# DAC.net
KiCad netlist of a schematic drawn in Altium Designer
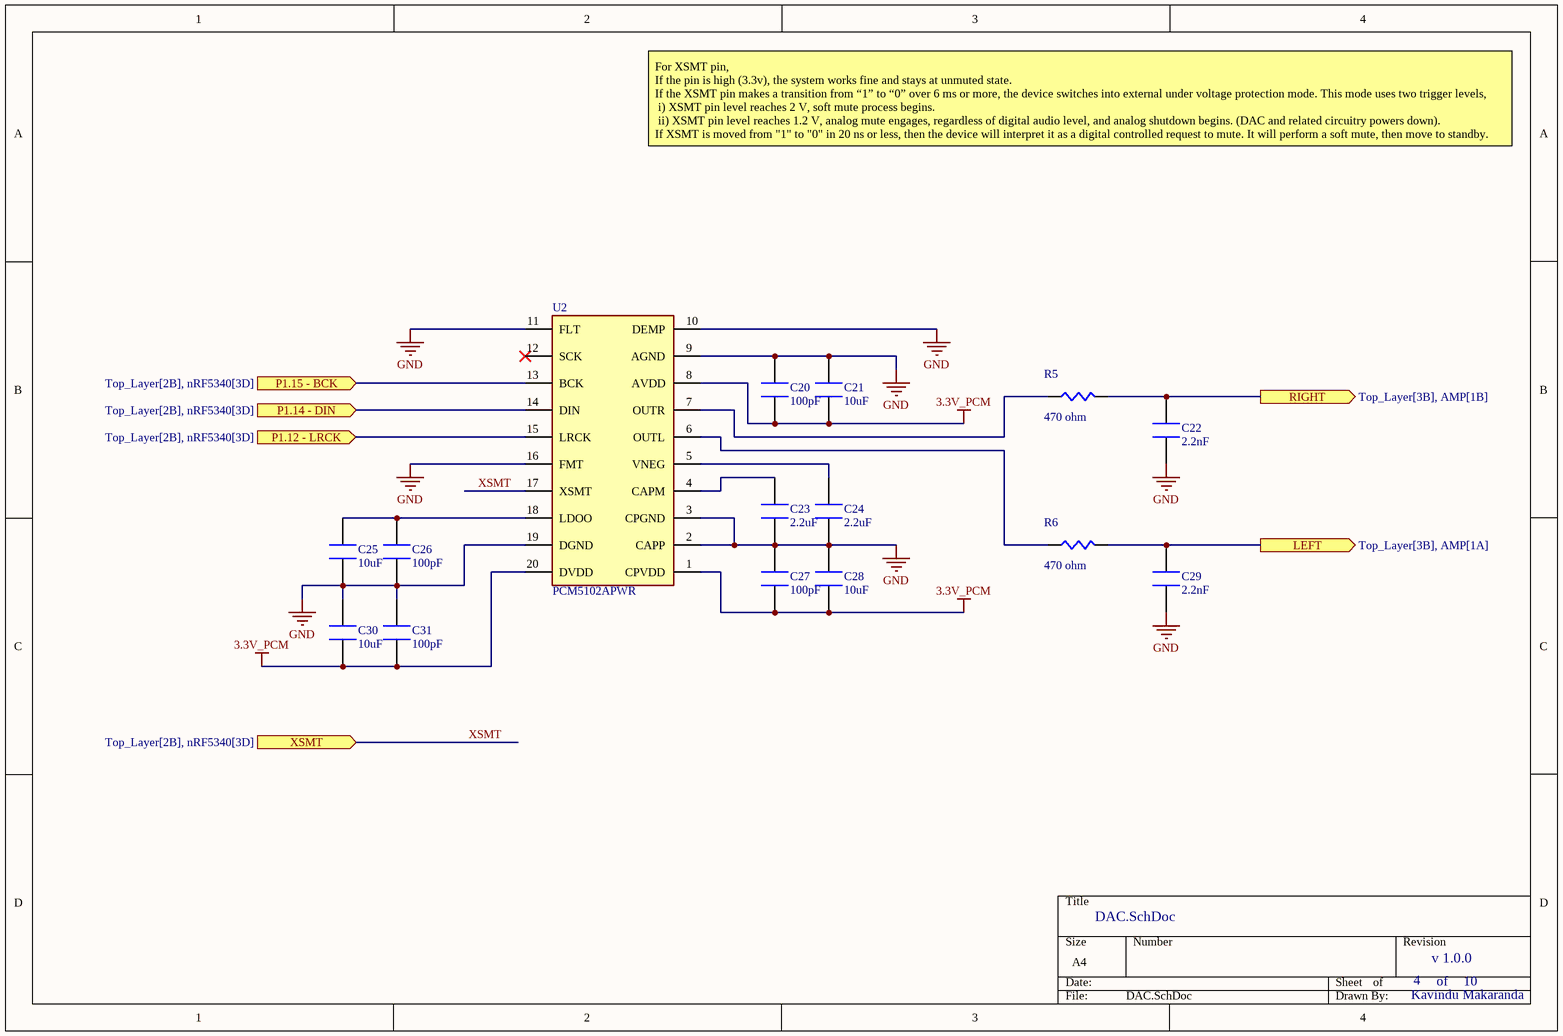
[diagram p0: DAC.SchDoc]

(export (version "E")
  (design (tool "Eeschema 10.0.6"))
  (components
    (comp (ref "C20")
      (value "100pF")
      (footprint "CAPC0603X8N")
      (libsource (lib "Schlib1") (part "CC0603_100pF_X7R"))
    )
    (comp (ref "C21")
      (value "10uF")
      (footprint "CAPC0805X14N")
      (description "C95841, CL21B106KOQNNNE, 10uF 16V X7R ±10% 0805 Multilayer Ceramic Capacitors MLCC - SMD/SMT ROHS")
      (libsource (lib "Schlib1") (part "CC0805_10uF_X7R"))
    )
    (comp (ref "C22")
      (value "2.2nF")
      (footprint "CAPC0603X8N")
      (libsource (lib "Schlib1") (part "CC0603_2.2nF_NPO"))
    )
    (comp (ref "C23")
      (value "2.2uF")
      (footprint "CAP0805X13N")
      (description "C19110 ,CL21B225KAFNNNE, 2.2uF 25V X7R ±10% 0805 Multilayer Ceramic Capacitors MLCC - SMD/SMT ROHS")
      (libsource (lib "Schlib1") (part "CC0805_2.2uF_X7R"))
    )
    (comp (ref "C24")
      (value "2.2uF")
      (footprint "CAP0805X13N")
      (description "C19110 ,CL21B225KAFNNNE, 2.2uF 25V X7R ±10% 0805 Multilayer Ceramic Capacitors MLCC - SMD/SMT ROHS")
      (libsource (lib "Schlib1") (part "CC0805_2.2uF_X7R"))
    )
    (comp (ref "C25")
      (value "10uF")
      (footprint "CAPC0805X14N")
      (description "C95841, CL21B106KOQNNNE, 10uF 16V X7R ±10% 0805 Multilayer Ceramic Capacitors MLCC - SMD/SMT ROHS")
      (libsource (lib "Schlib1") (part "CC0805_10uF_X7R"))
    )
    (comp (ref "C26")
      (value "100pF")
      (footprint "CAPC0603X8N")
      (libsource (lib "Schlib1") (part "CC0603_100pF_X7R"))
    )
    (comp (ref "C27")
      (value "100pF")
      (footprint "CAPC0603X8N")
      (libsource (lib "Schlib1") (part "CC0603_100pF_X7R"))
    )
    (comp (ref "C28")
      (value "10uF")
      (footprint "CAPC0805X14N")
      (description "C95841, CL21B106KOQNNNE, 10uF 16V X7R ±10% 0805 Multilayer Ceramic Capacitors MLCC - SMD/SMT ROHS")
      (libsource (lib "Schlib1") (part "CC0805_10uF_X7R"))
    )
    (comp (ref "C29")
      (value "2.2nF")
      (footprint "CAPC0603X8N")
      (libsource (lib "Schlib1") (part "CC0603_2.2nF_NPO"))
    )
    (comp (ref "C30")
      (value "10uF")
      (footprint "CAPC0805X14N")
      (description "C95841, CL21B106KOQNNNE, 10uF 16V X7R ±10% 0805 Multilayer Ceramic Capacitors MLCC - SMD/SMT ROHS")
      (libsource (lib "Schlib1") (part "CC0805_10uF_X7R"))
    )
    (comp (ref "C31")
      (value "100pF")
      (footprint "CAPC0603X8N")
      (libsource (lib "Schlib1") (part "CC0603_100pF_X7R"))
    )
    (comp (ref "R5")
      (value "470 ohm")
      (footprint "RECS0603X45N")
      (libsource (lib "Schlib1") (part "RESC0603_470_THIN"))
    )
    (comp (ref "R6")
      (value "470 ohm")
      (footprint "RECS0603X45N")
      (libsource (lib "Schlib1") (part "RESC0603_470_THIN"))
    )
    (comp (ref "U2")
      (value "PCM5102APWR")
      (footprint "SOP65P640X120-20N")
      (fields (field (name "MOUSER PART NUMBER") "595-PCM5102APWR"))
      (libsource (lib "Schlib1") (part "PCM5102APWR"))
    )
  )
  (nets
    (net (code "1") (name "/LEFT") (class "Default")
      (node (ref "C29") (pin "2") (pinfunction "2_2") (pintype "passive"))
      (node (ref "R6") (pin "2") (pinfunction "2_2") (pintype "passive"))
    )
    (net (code "2") (name "/P1.12 - LRCK") (class "Default")
      (node (ref "U2") (pin "15") (pinfunction "LRCK_15") (pintype "passive"))
    )
    (net (code "3") (name "/P1.14 - DIN") (class "Default")
      (node (ref "U2") (pin "14") (pinfunction "DIN_14") (pintype "passive"))
    )
    (net (code "4") (name "/P1.15 - BCK") (class "Default")
      (node (ref "U2") (pin "13") (pinfunction "BCK_13") (pintype "passive"))
    )
    (net (code "5") (name "/RIGHT") (class "Default")
      (node (ref "C22") (pin "2") (pinfunction "2_2") (pintype "passive"))
      (node (ref "R5") (pin "2") (pinfunction "2_2") (pintype "passive"))
    )
    (net (code "6") (name "/XSMT") (class "Default")
      (node (ref "U2") (pin "17") (pinfunction "XSMT_17") (pintype "passive"))
    )
    (net (code "7") (name "3.3V_PCM") (class "Default")
      (node (ref "C20") (pin "1") (pinfunction "1_1") (pintype "passive"))
      (node (ref "C21") (pin "1") (pinfunction "1_1") (pintype "passive"))
      (node (ref "C27") (pin "1") (pinfunction "1_1") (pintype "passive"))
      (node (ref "C28") (pin "1") (pinfunction "1_1") (pintype "passive"))
      (node (ref "C30") (pin "1") (pinfunction "1_1") (pintype "passive"))
      (node (ref "C31") (pin "1") (pinfunction "1_1") (pintype "passive"))
      (node (ref "U2") (pin "1") (pinfunction "CPVDD_1") (pintype "passive"))
      (node (ref "U2") (pin "20") (pinfunction "DVDD_20") (pintype "passive"))
      (node (ref "U2") (pin "8") (pinfunction "AVDD_8") (pintype "passive"))
    )
    (net (code "8") (name "GND") (class "Default")
      (node (ref "C20") (pin "2") (pinfunction "2_2") (pintype "passive"))
      (node (ref "C21") (pin "2") (pinfunction "2_2") (pintype "passive"))
      (node (ref "C22") (pin "1") (pinfunction "1_1") (pintype "passive"))
      (node (ref "C23") (pin "1") (pinfunction "1_1") (pintype "passive"))
      (node (ref "C24") (pin "1") (pinfunction "1_1") (pintype "passive"))
      (node (ref "C25") (pin "1") (pinfunction "1_1") (pintype "passive"))
      (node (ref "C26") (pin "1") (pinfunction "1_1") (pintype "passive"))
      (node (ref "C27") (pin "2") (pinfunction "2_2") (pintype "passive"))
      (node (ref "C28") (pin "2") (pinfunction "2_2") (pintype "passive"))
      (node (ref "C29") (pin "1") (pinfunction "1_1") (pintype "passive"))
      (node (ref "C30") (pin "2") (pinfunction "2_2") (pintype "passive"))
      (node (ref "C31") (pin "2") (pinfunction "2_2") (pintype "passive"))
      (node (ref "U2") (pin "10") (pinfunction "DEMP_10") (pintype "passive"))
      (node (ref "U2") (pin "11") (pinfunction "FLT_11") (pintype "passive"))
      (node (ref "U2") (pin "16") (pinfunction "FMT_16") (pintype "passive"))
      (node (ref "U2") (pin "19") (pinfunction "DGND_19") (pintype "passive"))
      (node (ref "U2") (pin "2") (pinfunction "CAPP_2") (pintype "passive"))
      (node (ref "U2") (pin "3") (pinfunction "CPGND_3") (pintype "passive"))
      (node (ref "U2") (pin "9") (pinfunction "AGND_9") (pintype "passive"))
    )
    (net (code "9") (name "Net-(U2-CAPM)") (class "Default")
      (node (ref "C23") (pin "2") (pinfunction "2_2") (pintype "passive"))
      (node (ref "U2") (pin "4") (pinfunction "CAPM_4") (pintype "passive"))
    )
    (net (code "10") (name "Net-(U2-LDOO)") (class "Default")
      (node (ref "C25") (pin "2") (pinfunction "2_2") (pintype "passive"))
      (node (ref "C26") (pin "2") (pinfunction "2_2") (pintype "passive"))
      (node (ref "U2") (pin "18") (pinfunction "LDOO_18") (pintype "passive"))
    )
    (net (code "11") (name "Net-(U2-OUTL)") (class "Default")
      (node (ref "R6") (pin "1") (pinfunction "1_1") (pintype "passive"))
      (node (ref "U2") (pin "6") (pinfunction "OUTL_6") (pintype "passive"))
    )
    (net (code "12") (name "Net-(U2-OUTR)") (class "Default")
      (node (ref "R5") (pin "1") (pinfunction "1_1") (pintype "passive"))
      (node (ref "U2") (pin "7") (pinfunction "OUTR_7") (pintype "passive"))
    )
    (net (code "13") (name "Net-(U2-VNEG)") (class "Default")
      (node (ref "C24") (pin "2") (pinfunction "2_2") (pintype "passive"))
      (node (ref "U2") (pin "5") (pinfunction "VNEG_5") (pintype "passive"))
    )
    (net (code "14") (name "unconnected-(U2-SCK-Pad12)") (class "Default")
      (node (ref "U2") (pin "12") (pinfunction "SCK_12") (pintype "passive+no_connect"))
    )
  )
)
